# NIR_Schematic.net
KiCad netlist of a schematic drawn in EasyEDA
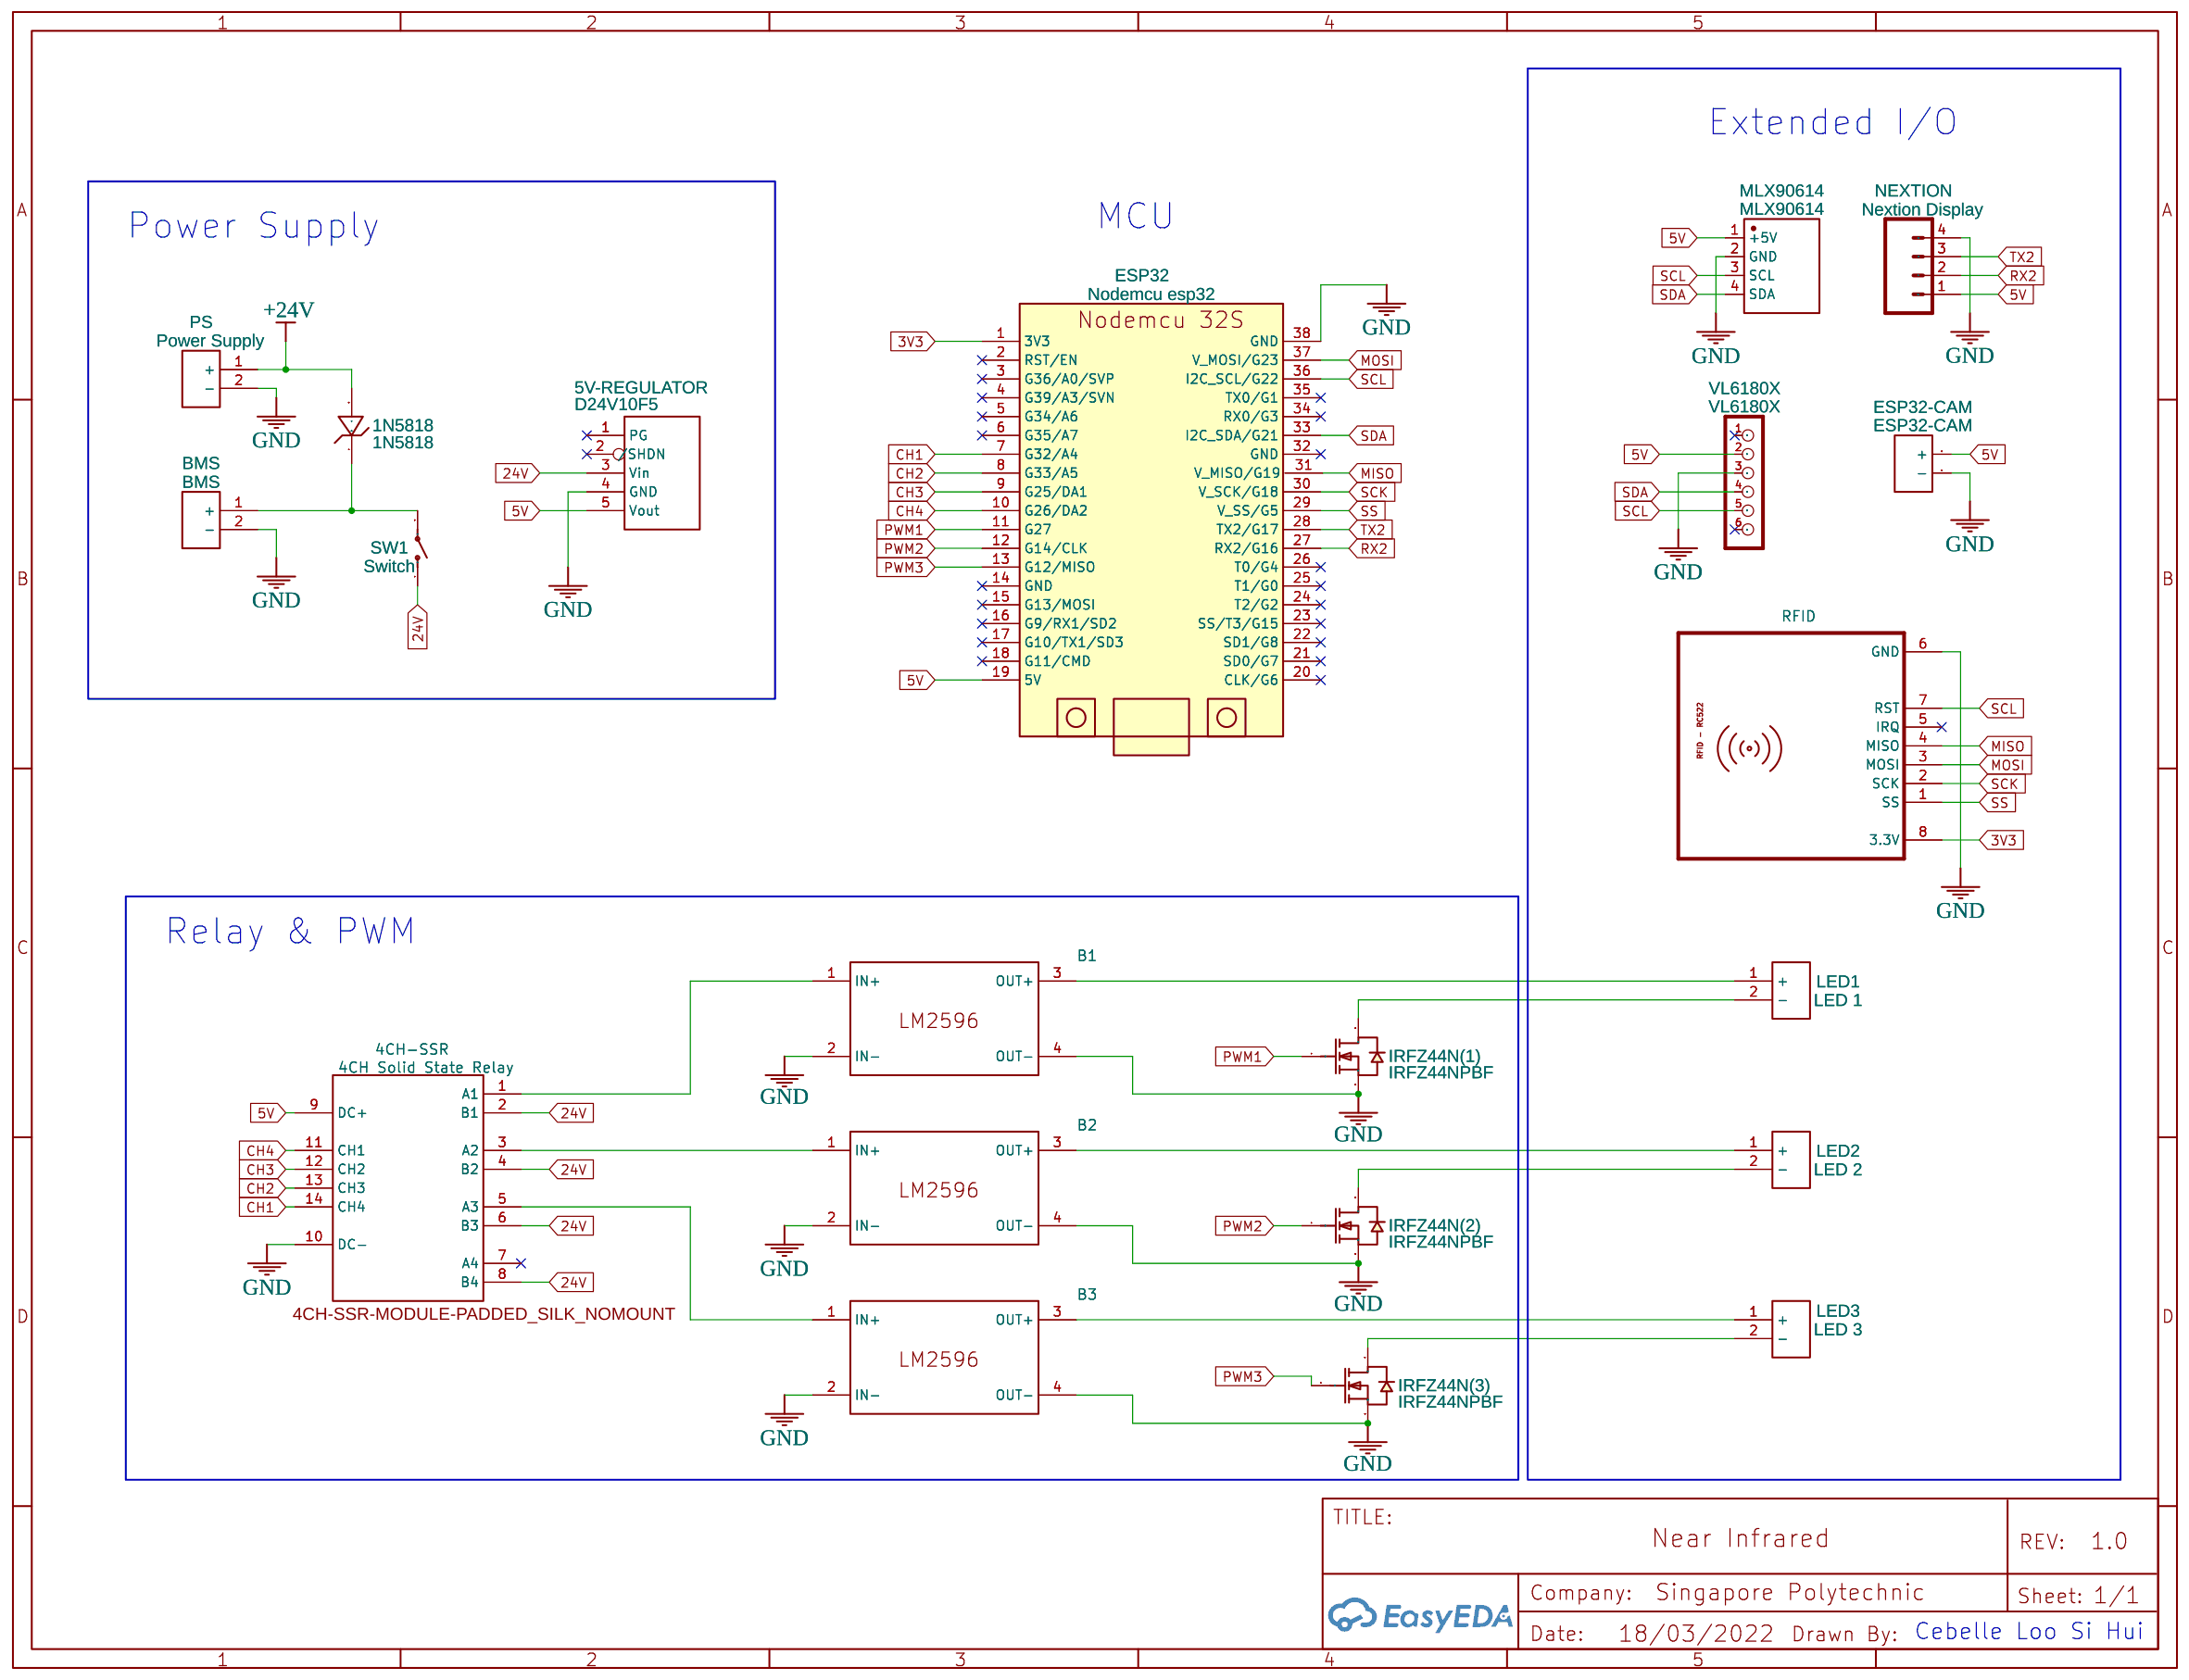
[diagram p0: schematic sheet]

(export (version "E")
  (design (tool "Eeschema 10.0.6"))
  (components
    (comp (ref "1N5818")
      (value "1N5818")
      (fields (field (name "BOM_Supplier Part") "C402217"))
      (libsource (lib "") (part "1N5818"))
    )
    (comp (ref "4CH-SSR") (value "4CH Solid State Relay") (libsource (lib "") (part "Unknown_210_-255")))
    (comp (ref "5V-REGULATOR") (value "D24V10F5") (libsource (lib "") (part "D24V10F5")))
    (comp (ref "B1") (value "NO") (libsource (lib "") (part "Unknown_495_-345")))
    (comp (ref "B2") (value "NO") (libsource (lib "") (part "Unknown_495_-255")))
    (comp (ref "B3") (value "NO") (libsource (lib "") (part "Unknown_495_-165")))
    (comp (ref "BMS")
      (value "BMS")
      (fields
        (field (name "BOM_Manufacturer Part") "WJ103-5.00-2P")
        (field (name "BOM_Supplier Part") "C8439")
      )
      (libsource (lib "") (part "WJ103-5.00-2P"))
    )
    (comp (ref "ESP32") (value "Nodemcu esp32") (libsource (lib "") (part "Nodemcu esp32")))
    (comp (ref "ESP32-CAM")
      (value "ESP32-CAM")
      (fields
        (field (name "BOM_Manufacturer Part") "2.54-1*2PFemale")
        (field (name "BOM_Supplier Part") "C49661")
      )
      (libsource (lib "") (part "Header-Female-2.54_1x2"))
    )
    (comp (ref "IRFZ44N(1)")
      (value "IRFZ44NPBF")
      (fields (field (name "BOM_Supplier Part") "C2586"))
      (libsource (lib "") (part "IRFZ44NPBF"))
    )
    (comp (ref "IRFZ44N(2)")
      (value "IRFZ44NPBF")
      (fields (field (name "BOM_Supplier Part") "C2586"))
      (libsource (lib "") (part "IRFZ44NPBF_1"))
    )
    (comp (ref "IRFZ44N(3)")
      (value "IRFZ44NPBF")
      (fields (field (name "BOM_Supplier Part") "C2586"))
      (libsource (lib "") (part "IRFZ44NPBF_2"))
    )
    (comp (ref "LED1")
      (value "LED 1")
      (fields
        (field (name "BOM_Manufacturer Part") "WJ103-5.00-2P")
        (field (name "BOM_Supplier Part") "C8439")
      )
      (libsource (lib "") (part "WJ103-5.00-2P_1"))
    )
    (comp (ref "LED2")
      (value "LED 2")
      (fields
        (field (name "BOM_Manufacturer Part") "WJ103-5.00-2P")
        (field (name "BOM_Supplier Part") "C8439")
      )
      (libsource (lib "") (part "WJ103-5.00-2P_1"))
    )
    (comp (ref "LED3")
      (value "LED 3")
      (fields
        (field (name "BOM_Manufacturer Part") "WJ103-5.00-2P")
        (field (name "BOM_Supplier Part") "C8439")
      )
      (libsource (lib "") (part "WJ103-5.00-2P_1"))
    )
    (comp (ref "MLX90614")
      (value "MLX90614")
      (fields
        (field (name "BOM_Manufacturer Part") "RE-H042TD-1190(LF)(SN)")
        (field (name "BOM_Supplier Part") "C265319")
      )
      (libsource (lib "") (part "RE-H042TD-1190(LF)(SN)"))
    )
    (comp (ref "NEXTION") (value "Nextion Display") (libsource (lib "") (part "M04POLAR")))
    (comp (ref "PS")
      (value "Power Supply")
      (fields
        (field (name "BOM_Manufacturer Part") "WJ103-5.00-2P")
        (field (name "BOM_Supplier Part") "C8439")
      )
      (libsource (lib "") (part "WJ103-5.00-2P_2"))
    )
    (comp (ref "RFID") (value "NO") (libsource (lib "") (part "Unknown_954_-490")))
    (comp (ref "SW1")
      (value "Switch")
      (fields (field (name "BOM_Manufacturer Part") "KCD1-11-1.5x1cm"))
      (libsource (lib "") (part "SWITCH-2P-SPST-Rocker-10x15mm"))
    )
    (comp (ref "VL6180X") (value "VL6180X") (libsource (lib "") (part "CON_HEADER_1X06-PTH")))
  )
  (nets
    (net (code "1") (name "+24V") (class "Default")
      (node (ref "1N5818") (pin "2") (pinfunction "A_2") (pintype "unspecified"))
      (node (ref "PS") (pin "1") (pinfunction "+_1") (pintype "unspecified"))
    )
    (net (code "2") (name "3V3") (class "Default")
      (node (ref "ESP32") (pin "1") (pinfunction "3V3_1") (pintype "passive"))
      (node (ref "RFID") (pin "8") (pinfunction "3.3V_8") (pintype "unspecified"))
    )
    (net (code "3") (name "5V") (class "Default")
      (node (ref "4CH-SSR") (pin "9") (pinfunction "DC+_9") (pintype "unspecified"))
      (node (ref "5V-REGULATOR") (pin "5") (pinfunction "Vout_5") (pintype "unspecified"))
      (node (ref "ESP32") (pin "19") (pinfunction "5V_19") (pintype "passive"))
      (node (ref "ESP32-CAM") (pin "2") (pinfunction "+_2") (pintype "input"))
      (node (ref "MLX90614") (pin "1") (pinfunction "+5V_1") (pintype "unspecified"))
      (node (ref "NEXTION") (pin "1") (pinfunction "GND_1") (pintype "unspecified"))
      (node (ref "VL6180X") (pin "2") (pinfunction "VIN_2") (pintype "unspecified"))
    )
    (net (code "4") (name "24V") (class "Default")
      (node (ref "4CH-SSR") (pin "2") (pinfunction "B1_2") (pintype "unspecified"))
      (node (ref "4CH-SSR") (pin "4") (pinfunction "B2_4") (pintype "unspecified"))
      (node (ref "4CH-SSR") (pin "6") (pinfunction "B3_6") (pintype "unspecified"))
      (node (ref "4CH-SSR") (pin "8") (pinfunction "B4_8") (pintype "unspecified"))
      (node (ref "5V-REGULATOR") (pin "3") (pinfunction "Vin_3") (pintype "unspecified"))
      (node (ref "SW1") (pin "1") (pinfunction "O_1") (pintype "unspecified"))
    )
    (net (code "5") (name "CH1") (class "Default")
      (node (ref "4CH-SSR") (pin "14") (pinfunction "CH4_14") (pintype "unspecified"))
      (node (ref "ESP32") (pin "7") (pinfunction "G32/A4_7") (pintype "bidirectional"))
    )
    (net (code "6") (name "CH2") (class "Default")
      (node (ref "4CH-SSR") (pin "13") (pinfunction "CH3_13") (pintype "unspecified"))
      (node (ref "ESP32") (pin "8") (pinfunction "G33/A5_8") (pintype "bidirectional"))
    )
    (net (code "7") (name "CH3") (class "Default")
      (node (ref "4CH-SSR") (pin "12") (pinfunction "CH2_12") (pintype "unspecified"))
      (node (ref "ESP32") (pin "9") (pinfunction "G25/DA1_9") (pintype "bidirectional"))
    )
    (net (code "8") (name "CH4") (class "Default")
      (node (ref "4CH-SSR") (pin "11") (pinfunction "CH1_11") (pintype "unspecified"))
      (node (ref "ESP32") (pin "10") (pinfunction "G26/DA2_10") (pintype "bidirectional"))
    )
    (net (code "9") (name "GND") (class "Default")
      (node (ref "4CH-SSR") (pin "10") (pinfunction "DC-_10") (pintype "unspecified"))
      (node (ref "5V-REGULATOR") (pin "4") (pinfunction "GND_4") (pintype "unspecified"))
      (node (ref "B1") (pin "2") (pinfunction "IN-_2") (pintype "unspecified"))
      (node (ref "B1") (pin "4") (pinfunction "OUT-_4") (pintype "unspecified"))
      (node (ref "B2") (pin "2") (pinfunction "IN-_2") (pintype "unspecified"))
      (node (ref "B2") (pin "4") (pinfunction "OUT-_4") (pintype "unspecified"))
      (node (ref "B3") (pin "2") (pinfunction "IN-_2") (pintype "unspecified"))
      (node (ref "B3") (pin "4") (pinfunction "OUT-_4") (pintype "unspecified"))
      (node (ref "BMS") (pin "2") (pinfunction "-_2") (pintype "unspecified"))
      (node (ref "ESP32") (pin "38") (pinfunction "GND_38") (pintype "passive"))
      (node (ref "ESP32-CAM") (pin "1") (pinfunction "-_1") (pintype "input"))
      (node (ref "IRFZ44N(1)") (pin "3") (pinfunction "S_3") (pintype "unspecified"))
      (node (ref "IRFZ44N(2)") (pin "3") (pinfunction "S_3") (pintype "unspecified"))
      (node (ref "IRFZ44N(3)") (pin "3") (pinfunction "S_3") (pintype "unspecified"))
      (node (ref "MLX90614") (pin "2") (pinfunction "GND_2") (pintype "unspecified"))
      (node (ref "NEXTION") (pin "4") (pinfunction "+5V_4") (pintype "unspecified"))
      (node (ref "PS") (pin "2") (pinfunction "-_2") (pintype "unspecified"))
      (node (ref "RFID") (pin "6") (pinfunction "GND_6") (pintype "unspecified"))
      (node (ref "VL6180X") (pin "3") (pinfunction "GND_3") (pintype "unspecified"))
    )
    (net (code "10") (name "MISO") (class "Default")
      (node (ref "ESP32") (pin "31") (pinfunction "V_MISO/G19_31") (pintype "bidirectional"))
      (node (ref "RFID") (pin "4") (pinfunction "MISO_4") (pintype "unspecified"))
    )
    (net (code "11") (name "MOSI") (class "Default")
      (node (ref "ESP32") (pin "37") (pinfunction "V_MOSI/G23_37") (pintype "bidirectional"))
      (node (ref "RFID") (pin "3") (pinfunction "MOSI_3") (pintype "unspecified"))
    )
    (net (code "12") (name "Net-(1N5818-C)") (class "Default")
      (node (ref "1N5818") (pin "1") (pinfunction "C_1") (pintype "unspecified"))
      (node (ref "BMS") (pin "1") (pinfunction "+_1") (pintype "unspecified"))
      (node (ref "SW1") (pin "2") (pinfunction "P_2") (pintype "unspecified"))
    )
    (net (code "13") (name "Net-(4CH-SSR-A1)") (class "Default")
      (node (ref "4CH-SSR") (pin "1") (pinfunction "A1_1") (pintype "unspecified"))
      (node (ref "B1") (pin "1") (pinfunction "IN+_1") (pintype "unspecified"))
    )
    (net (code "14") (name "Net-(4CH-SSR-A2)") (class "Default")
      (node (ref "4CH-SSR") (pin "3") (pinfunction "A2_3") (pintype "unspecified"))
      (node (ref "B2") (pin "1") (pinfunction "IN+_1") (pintype "unspecified"))
    )
    (net (code "15") (name "Net-(4CH-SSR-A3)") (class "Default")
      (node (ref "4CH-SSR") (pin "5") (pinfunction "A3_5") (pintype "unspecified"))
      (node (ref "B3") (pin "1") (pinfunction "IN+_1") (pintype "unspecified"))
    )
    (net (code "16") (name "Net-(B1-OUT+)") (class "Default")
      (node (ref "B1") (pin "3") (pinfunction "OUT+_3") (pintype "unspecified"))
      (node (ref "LED1") (pin "1") (pinfunction "+_1") (pintype "unspecified"))
    )
    (net (code "17") (name "Net-(B2-OUT+)") (class "Default")
      (node (ref "B2") (pin "3") (pinfunction "OUT+_3") (pintype "unspecified"))
      (node (ref "LED2") (pin "1") (pinfunction "+_1") (pintype "unspecified"))
    )
    (net (code "18") (name "Net-(B3-OUT+)") (class "Default")
      (node (ref "B3") (pin "3") (pinfunction "OUT+_3") (pintype "unspecified"))
      (node (ref "LED3") (pin "1") (pinfunction "+_1") (pintype "unspecified"))
    )
    (net (code "19") (name "Net-(IRFZ44N(1)-D)") (class "Default")
      (node (ref "IRFZ44N(1)") (pin "2") (pinfunction "D_2") (pintype "unspecified"))
      (node (ref "LED1") (pin "2") (pinfunction "-_2") (pintype "unspecified"))
    )
    (net (code "20") (name "Net-(IRFZ44N(2)-D)") (class "Default")
      (node (ref "IRFZ44N(2)") (pin "2") (pinfunction "D_2") (pintype "unspecified"))
      (node (ref "LED2") (pin "2") (pinfunction "-_2") (pintype "unspecified"))
    )
    (net (code "21") (name "Net-(IRFZ44N(3)-D)") (class "Default")
      (node (ref "IRFZ44N(3)") (pin "2") (pinfunction "D_2") (pintype "unspecified"))
      (node (ref "LED3") (pin "2") (pinfunction "-_2") (pintype "unspecified"))
    )
    (net (code "22") (name "PWM1") (class "Default")
      (node (ref "ESP32") (pin "11") (pinfunction "G27_11") (pintype "bidirectional"))
      (node (ref "IRFZ44N(1)") (pin "1") (pinfunction "G_1") (pintype "unspecified"))
    )
    (net (code "23") (name "PWM2") (class "Default")
      (node (ref "ESP32") (pin "12") (pinfunction "G14/CLK_12") (pintype "bidirectional"))
      (node (ref "IRFZ44N(2)") (pin "1") (pinfunction "G_1") (pintype "unspecified"))
    )
    (net (code "24") (name "PWM3") (class "Default")
      (node (ref "ESP32") (pin "13") (pinfunction "G12/MISO_13") (pintype "bidirectional"))
      (node (ref "IRFZ44N(3)") (pin "1") (pinfunction "G_1") (pintype "unspecified"))
    )
    (net (code "25") (name "RX2") (class "Default")
      (node (ref "ESP32") (pin "27") (pinfunction "RX2/G16_27") (pintype "bidirectional"))
      (node (ref "NEXTION") (pin "2") (pinfunction "RX_2") (pintype "unspecified"))
    )
    (net (code "26") (name "SCK") (class "Default")
      (node (ref "ESP32") (pin "30") (pinfunction "V_SCK/G18_30") (pintype "bidirectional"))
      (node (ref "RFID") (pin "2") (pinfunction "SCK_2") (pintype "unspecified"))
    )
    (net (code "27") (name "SCL") (class "Default")
      (node (ref "ESP32") (pin "36") (pinfunction "I2C_SCL/G22_36") (pintype "bidirectional"))
      (node (ref "MLX90614") (pin "3") (pinfunction "SCL_3") (pintype "unspecified"))
      (node (ref "RFID") (pin "7") (pinfunction "RST_7") (pintype "unspecified"))
      (node (ref "VL6180X") (pin "5") (pinfunction "SCL_5") (pintype "unspecified"))
    )
    (net (code "28") (name "SDA") (class "Default")
      (node (ref "ESP32") (pin "33") (pinfunction "I2C_SDA/G21_33") (pintype "bidirectional"))
      (node (ref "MLX90614") (pin "4") (pinfunction "SDA_4") (pintype "unspecified"))
      (node (ref "VL6180X") (pin "4") (pinfunction "SDA_4") (pintype "unspecified"))
    )
    (net (code "29") (name "SS") (class "Default")
      (node (ref "ESP32") (pin "29") (pinfunction "V_SS/G5_29") (pintype "bidirectional"))
      (node (ref "RFID") (pin "1") (pinfunction "SS_1") (pintype "unspecified"))
    )
    (net (code "30") (name "TX2") (class "Default")
      (node (ref "ESP32") (pin "28") (pinfunction "TX2/G17_28") (pintype "bidirectional"))
      (node (ref "NEXTION") (pin "3") (pinfunction "TX_3") (pintype "unspecified"))
    )
    (net (code "31") (name "unconnected-(4CH-SSR-A4-Pad7)") (class "Default")
      (node (ref "4CH-SSR") (pin "7") (pinfunction "A4_7") (pintype "unspecified+no_connect"))
    )
    (net (code "32") (name "unconnected-(5V-REGULATOR-PG-Pad1)") (class "Default")
      (node (ref "5V-REGULATOR") (pin "1") (pinfunction "PG_1") (pintype "unspecified+no_connect"))
    )
    (net (code "33") (name "unconnected-(5V-REGULATOR-{slash}SHDN-Pad2)") (class "Default")
      (node (ref "5V-REGULATOR") (pin "2") (pinfunction "/SHDN_2") (pintype "unspecified+no_connect"))
    )
    (net (code "34") (name "unconnected-(ESP32-CLK{slash}G6-Pad20)") (class "Default")
      (node (ref "ESP32") (pin "20") (pinfunction "CLK/G6_20") (pintype "bidirectional+no_connect"))
    )
    (net (code "35") (name "unconnected-(ESP32-G9{slash}RX1{slash}SD2-Pad16)") (class "Default")
      (node (ref "ESP32") (pin "16") (pinfunction "G9/RX1/SD2_16") (pintype "bidirectional+no_connect"))
    )
    (net (code "36") (name "unconnected-(ESP32-G10{slash}TX1{slash}SD3-Pad17)") (class "Default")
      (node (ref "ESP32") (pin "17") (pinfunction "G10/TX1/SD3_17") (pintype "bidirectional+no_connect"))
    )
    (net (code "37") (name "unconnected-(ESP32-G11{slash}CMD-Pad18)") (class "Default")
      (node (ref "ESP32") (pin "18") (pinfunction "G11/CMD_18") (pintype "bidirectional+no_connect"))
    )
    (net (code "38") (name "unconnected-(ESP32-G13{slash}MOSI-Pad15)") (class "Default")
      (node (ref "ESP32") (pin "15") (pinfunction "G13/MOSI_15") (pintype "bidirectional+no_connect"))
    )
    (net (code "39") (name "unconnected-(ESP32-G34{slash}A6-Pad5)") (class "Default")
      (node (ref "ESP32") (pin "5") (pinfunction "G34/A6_5") (pintype "bidirectional+no_connect"))
    )
    (net (code "40") (name "unconnected-(ESP32-G35{slash}A7-Pad6)") (class "Default")
      (node (ref "ESP32") (pin "6") (pinfunction "G35/A7_6") (pintype "bidirectional+no_connect"))
    )
    (net (code "41") (name "unconnected-(ESP32-G36{slash}A0{slash}SVP-Pad3)") (class "Default")
      (node (ref "ESP32") (pin "3") (pinfunction "G36/A0/SVP_3") (pintype "bidirectional+no_connect"))
    )
    (net (code "42") (name "unconnected-(ESP32-G39{slash}A3{slash}SVN-Pad4)") (class "Default")
      (node (ref "ESP32") (pin "4") (pinfunction "G39/A3/SVN_4") (pintype "bidirectional+no_connect"))
    )
    (net (code "43") (name "unconnected-(ESP32-GND-Pad14)") (class "Default")
      (node (ref "ESP32") (pin "14") (pinfunction "GND_14") (pintype "passive+no_connect"))
    )
    (net (code "44") (name "unconnected-(ESP32-GND-Pad32)") (class "Default")
      (node (ref "ESP32") (pin "32") (pinfunction "GND_32") (pintype "passive+no_connect"))
    )
    (net (code "45") (name "unconnected-(ESP32-RST{slash}EN-Pad2)") (class "Default")
      (node (ref "ESP32") (pin "2") (pinfunction "RST/EN_2") (pintype "bidirectional+no_connect"))
    )
    (net (code "46") (name "unconnected-(ESP32-RX0{slash}G3-Pad34)") (class "Default")
      (node (ref "ESP32") (pin "34") (pinfunction "RX0/G3_34") (pintype "bidirectional+no_connect"))
    )
    (net (code "47") (name "unconnected-(ESP32-SD0{slash}G7-Pad21)") (class "Default")
      (node (ref "ESP32") (pin "21") (pinfunction "SD0/G7_21") (pintype "bidirectional+no_connect"))
    )
    (net (code "48") (name "unconnected-(ESP32-SD1{slash}G8-Pad22)") (class "Default")
      (node (ref "ESP32") (pin "22") (pinfunction "SD1/G8_22") (pintype "bidirectional+no_connect"))
    )
    (net (code "49") (name "unconnected-(ESP32-SS{slash}T3{slash}G15-Pad23)") (class "Default")
      (node (ref "ESP32") (pin "23") (pinfunction "SS/T3/G15_23") (pintype "bidirectional+no_connect"))
    )
    (net (code "50") (name "unconnected-(ESP32-T0{slash}G4-Pad26)") (class "Default")
      (node (ref "ESP32") (pin "26") (pinfunction "T0/G4_26") (pintype "bidirectional+no_connect"))
    )
    (net (code "51") (name "unconnected-(ESP32-T1{slash}G0-Pad25)") (class "Default")
      (node (ref "ESP32") (pin "25") (pinfunction "T1/G0_25") (pintype "bidirectional+no_connect"))
    )
    (net (code "52") (name "unconnected-(ESP32-T2{slash}G2-Pad24)") (class "Default")
      (node (ref "ESP32") (pin "24") (pinfunction "T2/G2_24") (pintype "bidirectional+no_connect"))
    )
    (net (code "53") (name "unconnected-(ESP32-TX0{slash}G1-Pad35)") (class "Default")
      (node (ref "ESP32") (pin "35") (pinfunction "TX0/G1_35") (pintype "bidirectional+no_connect"))
    )
    (net (code "54") (name "unconnected-(RFID-IRQ-Pad5)") (class "Default")
      (node (ref "RFID") (pin "5") (pinfunction "IRQ_5") (pintype "unspecified+no_connect"))
    )
    (net (code "55") (name "unconnected-(VL6180X-IO1-Pad6)") (class "Default")
      (node (ref "VL6180X") (pin "6") (pinfunction "IO1_6") (pintype "unspecified+no_connect"))
    )
    (net (code "56") (name "unconnected-(VL6180X-VDD-Pad1)") (class "Default")
      (node (ref "VL6180X") (pin "1") (pinfunction "VDD_1") (pintype "unspecified+no_connect"))
    )
  )
)
